# LM331.net
KiCad netlist of a schematic drawn in Altium Designer
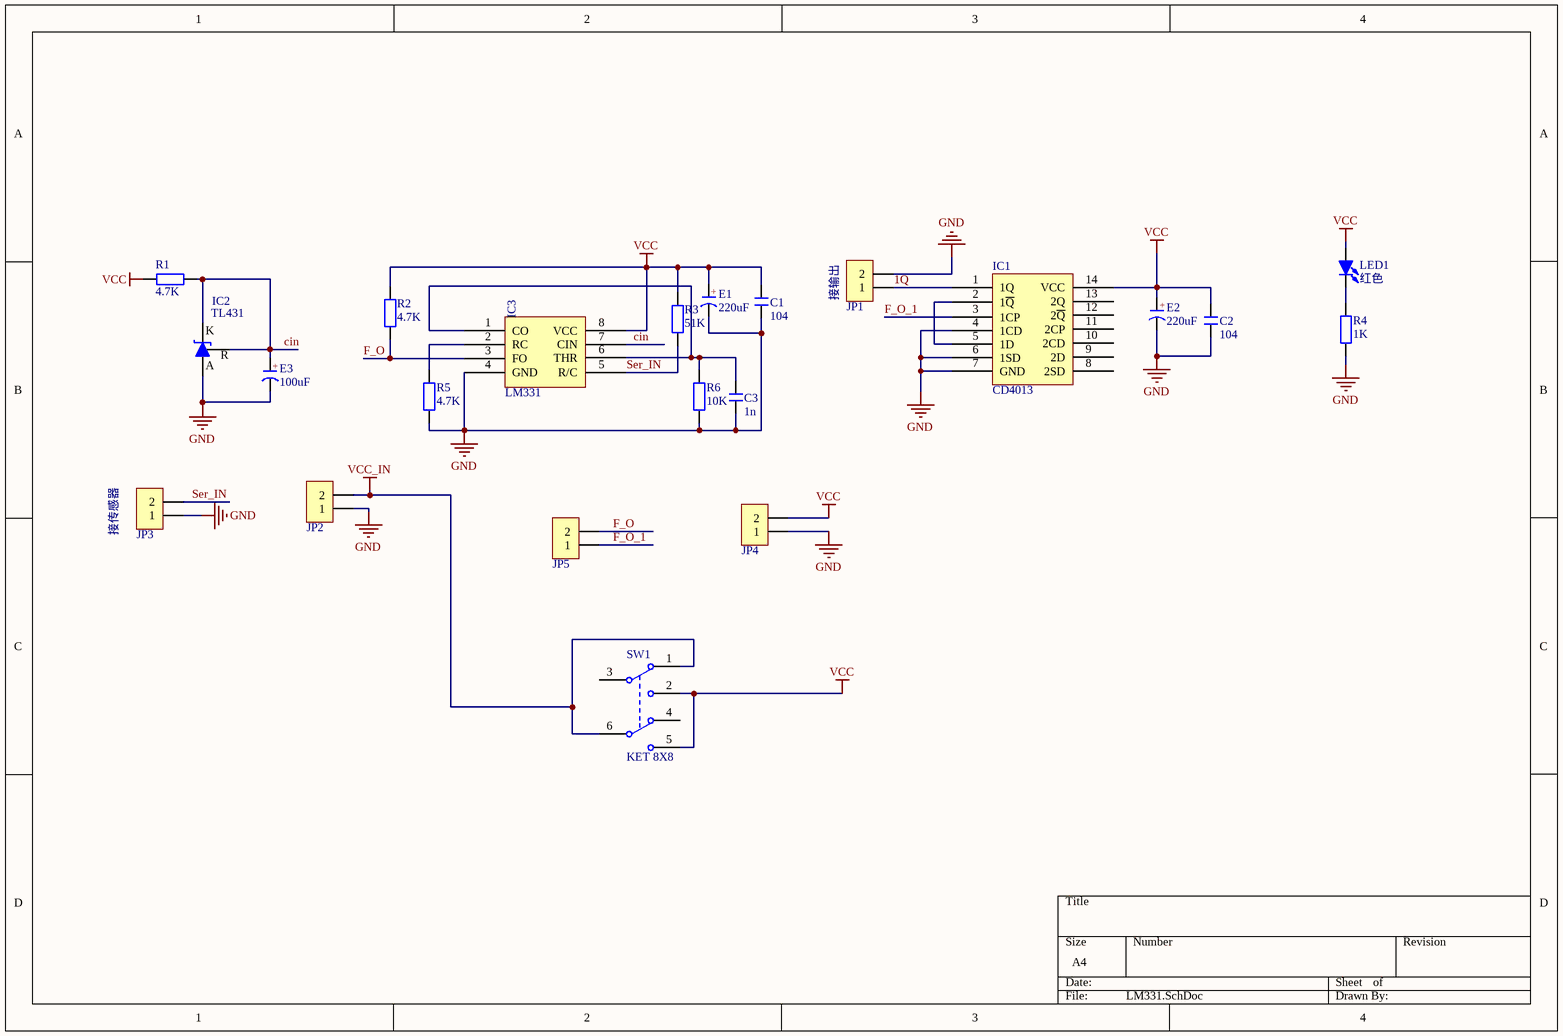
[diagram p0: LM331.SchDoc]

(export (version "E")
  (design (tool "Eeschema 10.0.6"))
  (components
    (comp (ref "C1")
      (value "104")
      (footprint "C 0805_M")
      (description "无极性贴片电容")
      (fields (field (name "版权归属") "源创客"))
      (libsource (lib "3.1   - 电阻-电容-电感") (part "C"))
    )
    (comp (ref "C2")
      (value "104")
      (footprint "C 0805_M")
      (description "无极性贴片电容")
      (fields (field (name "版权归属") "源创客"))
      (libsource (lib "3.1   - 电阻-电容-电感") (part "C"))
    )
    (comp (ref "C3")
      (value "1n")
      (footprint "C 0805_M")
      (description "无极性贴片电容")
      (fields (field (name "版权归属") "源创客"))
      (libsource (lib "3.1   - 电阻-电容-电感") (part "C"))
    )
    (comp (ref "E1")
      (value "220uF")
      (footprint "CAP 3.5*8*11.5")
      (description "直插电解电容")
      (fields (field (name "版权归属") "源创客"))
      (libsource (lib "3.1   - 电阻-电容-电感") (part "C-CAP"))
    )
    (comp (ref "E2")
      (value "220uF")
      (footprint "CAP 3.5*8*11.5")
      (description "直插电解电容")
      (fields (field (name "版权归属") "源创客"))
      (libsource (lib "3.1   - 电阻-电容-电感") (part "C-CAP"))
    )
    (comp (ref "E3")
      (value "100uF")
      (footprint "CAP 3.5*8*11.5")
      (description "直插电解电容")
      (fields (field (name "版权归属") "源创客"))
      (libsource (lib "3.1   - 电阻-电容-电感") (part "C-CAP"))
    )
    (comp (ref "IC1") (value "CD4013") (footprint "SOP14_M") (libsource (lib "1.1   - IC芯片") (part "CD4013")))
    (comp (ref "IC2")
      (value "TL431")
      (footprint "TO92A")
      (description "可调基准稳压芯片")
      (fields (field (name "版权归属") "源创客"))
      (libsource (lib "1.3   - 电源类芯片") (part "TL431-ID"))
    )
    (comp (ref "IC3")
      (value "LM331")
      (footprint "SOP8_M")
      (description "频率电压转换器")
      (libsource (lib "1.1   - IC芯片") (part "LM331"))
    )
    (comp (ref "JP1")
      (value "HDR-1X2")
      (footprint "XH2.54-LI-2P")
      (description "2P接插件")
      (fields (field (name "版权归属") "源创客"))
      (libsource (lib "4.5   - 接插件-脚距2.54") (part "Header 2"))
    )
    (comp (ref "JP2")
      (value "HDR-1X2")
      (footprint "XH2.54-LI-2P")
      (description "2P接插件")
      (fields (field (name "版权归属") "源创客"))
      (libsource (lib "4.5   - 接插件-脚距2.54") (part "Header 2"))
    )
    (comp (ref "JP3")
      (value "HDR-1X2")
      (footprint "KF2EDGK5.0-LI-2P")
      (description "2P接插件")
      (fields (field (name "版权归属") "源创客"))
      (libsource (lib "4.9   - 接插件-脚距5.0") (part "Header 2"))
    )
    (comp (ref "JP4")
      (value "HDR-1X2")
      (footprint "XH2.54-LI-2P")
      (description "2P接插件")
      (fields (field (name "版权归属") "源创客"))
      (libsource (lib "4.5   - 接插件-脚距2.54") (part "Header 2"))
    )
    (comp (ref "JP5")
      (value "HDR-1X2")
      (footprint "XH2.54-LI-2P")
      (description "2P接插件")
      (fields (field (name "版权归属") "源创客"))
      (libsource (lib "4.5   - 接插件-脚距2.54") (part "Header 2"))
    )
    (comp (ref "LED1")
      (value "红色")
      (footprint "LED 5MM-B")
      (description "5mm插件LED")
      (fields (field (name "版权归属") "源创客"))
      (libsource (lib "9.1   - LED") (part "LED-5MM"))
    )
    (comp (ref "R1")
      (value "4.7K")
      (footprint "R 0805_M")
      (description "贴片电阻")
      (fields (field (name "版权归属") "源创客"))
      (libsource (lib "3.1   - 电阻-电容-电感") (part "R"))
    )
    (comp (ref "R2")
      (value "4.7K")
      (footprint "R 0805_M")
      (description "贴片电阻")
      (fields (field (name "版权归属") "源创客"))
      (libsource (lib "3.1   - 电阻-电容-电感") (part "R"))
    )
    (comp (ref "R3")
      (value "51K")
      (footprint "RS 1/4W")
      (description "直插色环电阻")
      (fields (field (name "版权归属") "源创客"))
      (libsource (lib "3.1   - 电阻-电容-电感") (part "R-CRR"))
    )
    (comp (ref "R4")
      (value "1K")
      (footprint "RS 1/4W")
      (description "直插色环电阻")
      (fields (field (name "版权归属") "源创客"))
      (libsource (lib "3.1   - 电阻-电容-电感") (part "R-CRR"))
    )
    (comp (ref "R5")
      (value "4.7K")
      (footprint "R 0805_M")
      (description "贴片电阻")
      (fields (field (name "版权归属") "源创客"))
      (libsource (lib "3.1   - 电阻-电容-电感") (part "R"))
    )
    (comp (ref "R6")
      (value "10K")
      (footprint "R 0805_M")
      (description "贴片电阻")
      (fields (field (name "版权归属") "源创客"))
      (libsource (lib "3.1   - 电阻-电容-电感") (part "R"))
    )
    (comp (ref "SW1")
      (value "KET 8X8")
      (footprint "KFT DIP-8X8")
      (description "8*8自锁开关")
      (fields (field (name "版权归属") "源创客"))
      (libsource (lib "5.1   - 按键-开关") (part "KET 8X8"))
    )
  )
  (nets
    (net (code "1") (name "/1Q") (class "Default")
      (node (ref "IC1") (pin "1") (pinfunction "1Q_1") (pintype "passive"))
      (node (ref "JP1") (pin "1") (pinfunction "1_1") (pintype "passive"))
    )
    (net (code "2") (name "/F_O") (class "Default")
      (node (ref "IC3") (pin "3") (pinfunction "FO_3") (pintype "passive"))
      (node (ref "JP5") (pin "2") (pinfunction "2_2") (pintype "passive"))
      (node (ref "R2") (pin "1") (pinfunction "1_1") (pintype "passive"))
    )
    (net (code "3") (name "/F_O_1") (class "Default")
      (node (ref "IC1") (pin "3") (pinfunction "1CP_3") (pintype "passive"))
      (node (ref "JP5") (pin "1") (pinfunction "1_1") (pintype "passive"))
    )
    (net (code "4") (name "/Ser_IN") (class "Default")
      (node (ref "IC3") (pin "5") (pinfunction "R/C_5") (pintype "passive"))
      (node (ref "JP3") (pin "2") (pinfunction "2_2") (pintype "passive"))
      (node (ref "R3") (pin "1") (pinfunction "1_1") (pintype "passive"))
    )
    (net (code "5") (name "/cin") (class "Default")
      (node (ref "E3") (pin "1") (pinfunction "A_1") (pintype "passive"))
      (node (ref "IC2") (pin "1") (pinfunction "R_1") (pintype "passive"))
      (node (ref "IC2") (pin "3") (pinfunction "K_3") (pintype "passive"))
      (node (ref "IC3") (pin "7") (pinfunction "CIN_7") (pintype "passive"))
      (node (ref "R1") (pin "1") (pinfunction "1_1") (pintype "passive"))
    )
    (net (code "6") (name "GND") (class "Default")
      (node (ref "C1") (pin "1") (pinfunction "1_1") (pintype "passive"))
      (node (ref "C2") (pin "1") (pinfunction "1_1") (pintype "passive"))
      (node (ref "C3") (pin "1") (pinfunction "1_1") (pintype "passive"))
      (node (ref "E1") (pin "2") (pinfunction "K_2") (pintype "passive"))
      (node (ref "E2") (pin "2") (pinfunction "K_2") (pintype "passive"))
      (node (ref "E3") (pin "2") (pinfunction "K_2") (pintype "passive"))
      (node (ref "IC1") (pin "4") (pinfunction "1CD_4") (pintype "passive"))
      (node (ref "IC1") (pin "6") (pinfunction "1SD_6") (pintype "passive"))
      (node (ref "IC1") (pin "7") (pinfunction "GND_7") (pintype "passive"))
      (node (ref "IC2") (pin "2") (pinfunction "A_2") (pintype "passive"))
      (node (ref "IC3") (pin "4") (pinfunction "GND_4") (pintype "passive"))
      (node (ref "JP1") (pin "2") (pinfunction "2_2") (pintype "passive"))
      (node (ref "JP2") (pin "1") (pinfunction "1_1") (pintype "passive"))
      (node (ref "JP3") (pin "1") (pinfunction "1_1") (pintype "passive"))
      (node (ref "JP4") (pin "1") (pinfunction "1_1") (pintype "passive"))
      (node (ref "R4") (pin "1") (pinfunction "1_1") (pintype "passive"))
      (node (ref "R5") (pin "1") (pinfunction "1_1") (pintype "passive"))
      (node (ref "R6") (pin "1") (pinfunction "1_1") (pintype "passive"))
    )
    (net (code "7") (name "Net-(IC1-1D)") (class "Default")
      (node (ref "IC1") (pin "2") (pinfunction "1~{Q}_2") (pintype "passive"))
      (node (ref "IC1") (pin "5") (pinfunction "1D_5") (pintype "passive"))
    )
    (net (code "8") (name "Net-(IC3-CO)") (class "Default")
      (node (ref "C3") (pin "2") (pinfunction "2_2") (pintype "passive"))
      (node (ref "IC3") (pin "1") (pinfunction "CO_1") (pintype "passive"))
      (node (ref "IC3") (pin "6") (pinfunction "THR_6") (pintype "passive"))
      (node (ref "R6") (pin "2") (pinfunction "2_2") (pintype "passive"))
    )
    (net (code "9") (name "Net-(IC3-RC)") (class "Default")
      (node (ref "IC3") (pin "2") (pinfunction "RC_2") (pintype "passive"))
      (node (ref "R5") (pin "2") (pinfunction "2_2") (pintype "passive"))
    )
    (net (code "10") (name "Net-(LED1-K)") (class "Default")
      (node (ref "LED1") (pin "2") (pinfunction "K_2") (pintype "passive"))
      (node (ref "R4") (pin "2") (pinfunction "2_2") (pintype "passive"))
    )
    (net (code "11") (name "VCC") (class "Default")
      (node (ref "C1") (pin "2") (pinfunction "2_2") (pintype "passive"))
      (node (ref "C2") (pin "2") (pinfunction "2_2") (pintype "passive"))
      (node (ref "E1") (pin "1") (pinfunction "A_1") (pintype "passive"))
      (node (ref "E2") (pin "1") (pinfunction "A_1") (pintype "passive"))
      (node (ref "IC1") (pin "14") (pinfunction "VCC_14") (pintype "passive"))
      (node (ref "IC3") (pin "8") (pinfunction "VCC_8") (pintype "power_in"))
      (node (ref "JP4") (pin "2") (pinfunction "2_2") (pintype "passive"))
      (node (ref "LED1") (pin "1") (pinfunction "A_1") (pintype "passive"))
      (node (ref "R1") (pin "2") (pinfunction "2_2") (pintype "passive"))
      (node (ref "R2") (pin "2") (pinfunction "2_2") (pintype "passive"))
      (node (ref "R3") (pin "2") (pinfunction "2_2") (pintype "passive"))
      (node (ref "SW1") (pin "2") (pinfunction "COM2_2") (pintype "passive"))
      (node (ref "SW1") (pin "5") (pinfunction "COM2_5") (pintype "passive"))
    )
    (net (code "12") (name "VCC_IN") (class "Default")
      (node (ref "JP2") (pin "2") (pinfunction "2_2") (pintype "passive"))
      (node (ref "SW1") (pin "1") (pinfunction "NC1_1") (pintype "passive"))
      (node (ref "SW1") (pin "6") (pinfunction "NC2_6") (pintype "passive"))
    )
    (net (code "13") (name "unconnected-(IC1-2CD-Pad10)") (class "Default")
      (node (ref "IC1") (pin "10") (pinfunction "2CD_10") (pintype "passive"))
    )
    (net (code "14") (name "unconnected-(IC1-2CP-Pad11)") (class "Default")
      (node (ref "IC1") (pin "11") (pinfunction "2CP_11") (pintype "passive"))
    )
    (net (code "15") (name "unconnected-(IC1-2D-Pad9)") (class "Default")
      (node (ref "IC1") (pin "9") (pinfunction "2D_9") (pintype "passive"))
    )
    (net (code "16") (name "unconnected-(IC1-2Q-Pad13)") (class "Default")
      (node (ref "IC1") (pin "13") (pinfunction "2Q_13") (pintype "passive"))
    )
    (net (code "17") (name "unconnected-(IC1-2SD-Pad8)") (class "Default")
      (node (ref "IC1") (pin "8") (pinfunction "2SD_8") (pintype "passive"))
    )
    (net (code "18") (name "unconnected-(IC1-2~{Q}-Pad12)") (class "Default")
      (node (ref "IC1") (pin "12") (pinfunction "2~{Q}_12") (pintype "passive"))
    )
    (net (code "19") (name "unconnected-(SW1-NO1-Pad3)") (class "Default")
      (node (ref "SW1") (pin "3") (pinfunction "NO1_3") (pintype "passive"))
    )
    (net (code "20") (name "unconnected-(SW1-NO2-Pad4)") (class "Default")
      (node (ref "SW1") (pin "4") (pinfunction "NO2_4") (pintype "passive"))
    )
  )
)
